# 555timerschematic.net
KiCad netlist of a schematic drawn in EAGLE
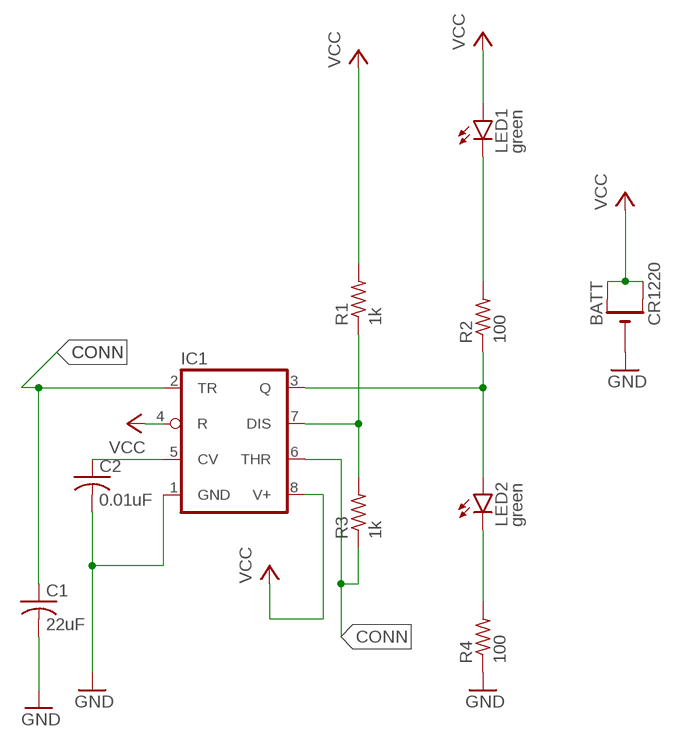
[diagram p0: schematic, sheet 1]

(export (version "E")
  (design (tool "Eeschema 10.0.6"))
  (components
    (comp (ref "BATT")
      (value "CR1220")
      (footprint "eagle-import:CR1220-SMD")
      (libsource (lib "eagle-import") (part "CR1220SMT"))
    )
    (comp (ref "C1")
      (value "22uF")
      (footprint "eagle-import:C0805")
      (libsource (lib "eagle-import") (part "C-USC0805"))
    )
    (comp (ref "C2")
      (value "0.01uF")
      (footprint "eagle-import:C0805")
      (libsource (lib "eagle-import") (part "C-USC0805"))
    )
    (comp (ref "IC1")
      (value "LM555D")
      (footprint "eagle-import:SO08")
      (libsource (lib "eagle-import") (part "555DLM"))
    )
    (comp (ref "LED1")
      (value "green")
      (footprint "eagle-import:CHIPLED_0805")
      (libsource (lib "eagle-import") (part "LEDCHIPLED_0805"))
    )
    (comp (ref "LED2")
      (value "green")
      (footprint "eagle-import:CHIPLED_0805")
      (libsource (lib "eagle-import") (part "LEDCHIPLED_0805"))
    )
    (comp (ref "R1")
      (value "1k")
      (footprint "eagle-import:R0805")
      (libsource (lib "eagle-import") (part "R-US_R0805"))
    )
    (comp (ref "R2")
      (value "100")
      (footprint "eagle-import:R0805")
      (libsource (lib "eagle-import") (part "R-US_R0805"))
    )
    (comp (ref "R3")
      (value "1k")
      (footprint "eagle-import:R0805")
      (libsource (lib "eagle-import") (part "R-US_R0805"))
    )
    (comp (ref "R4")
      (value "100")
      (footprint "eagle-import:R0805")
      (libsource (lib "eagle-import") (part "R-US_R0805"))
    )
  )
  (nets
    (net (code "1") (name "CONN") (class "Default")
      (node (ref "C1") (pin "1") (pinfunction "1_1") (pintype "passive"))
      (node (ref "IC1") (pin "2") (pinfunction "TR_2") (pintype "input"))
      (node (ref "IC1") (pin "6") (pinfunction "THR_6") (pintype "input"))
      (node (ref "R3") (pin "1") (pinfunction "1_1") (pintype "passive"))
    )
    (net (code "2") (name "GND") (class "Default")
      (node (ref "BATT") (pin "-") (pinfunction "-_-") (pintype "passive"))
      (node (ref "C1") (pin "2") (pinfunction "2_2") (pintype "passive"))
      (node (ref "C2") (pin "2") (pinfunction "2_2") (pintype "passive"))
      (node (ref "IC1") (pin "1") (pinfunction "GND_1") (pintype "power_in"))
      (node (ref "R4") (pin "1") (pinfunction "1_1") (pintype "passive"))
    )
    (net (code "3") (name "Net-(IC1-CV)") (class "Default")
      (node (ref "C2") (pin "1") (pinfunction "1_1") (pintype "passive"))
      (node (ref "IC1") (pin "5") (pinfunction "CV_5") (pintype "input"))
    )
    (net (code "4") (name "Net-(IC1-DIS)") (class "Default")
      (node (ref "IC1") (pin "7") (pinfunction "DIS_7") (pintype "input"))
      (node (ref "R1") (pin "1") (pinfunction "1_1") (pintype "passive"))
      (node (ref "R3") (pin "2") (pinfunction "2_2") (pintype "passive"))
    )
    (net (code "5") (name "Net-(IC1-Q)") (class "Default")
      (node (ref "IC1") (pin "3") (pinfunction "Q_3") (pintype "output"))
      (node (ref "LED2") (pin "A") (pinfunction "A_A") (pintype "passive"))
      (node (ref "R2") (pin "1") (pinfunction "1_1") (pintype "passive"))
    )
    (net (code "6") (name "Net-(LED1-PadC)") (class "Default")
      (node (ref "LED1") (pin "C") (pinfunction "C_C") (pintype "passive"))
      (node (ref "R2") (pin "2") (pinfunction "2_2") (pintype "passive"))
    )
    (net (code "7") (name "Net-(LED2-PadC)") (class "Default")
      (node (ref "LED2") (pin "C") (pinfunction "C_C") (pintype "passive"))
      (node (ref "R4") (pin "2") (pinfunction "2_2") (pintype "passive"))
    )
    (net (code "8") (name "VCC") (class "Default")
      (node (ref "BATT") (pin "+$1") (pinfunction "+_+$1") (pintype "passive"))
      (node (ref "BATT") (pin "+$2") (pinfunction "+1_+$2") (pintype "passive"))
      (node (ref "IC1") (pin "4") (pinfunction "R_4") (pintype "input"))
      (node (ref "IC1") (pin "8") (pinfunction "V+_8") (pintype "power_in"))
      (node (ref "LED1") (pin "A") (pinfunction "A_A") (pintype "passive"))
      (node (ref "R1") (pin "2") (pinfunction "2_2") (pintype "passive"))
    )
  )
)
